# 1-Schematic_Hack_Club_2.net
KiCad netlist of a schematic drawn in EasyEDA
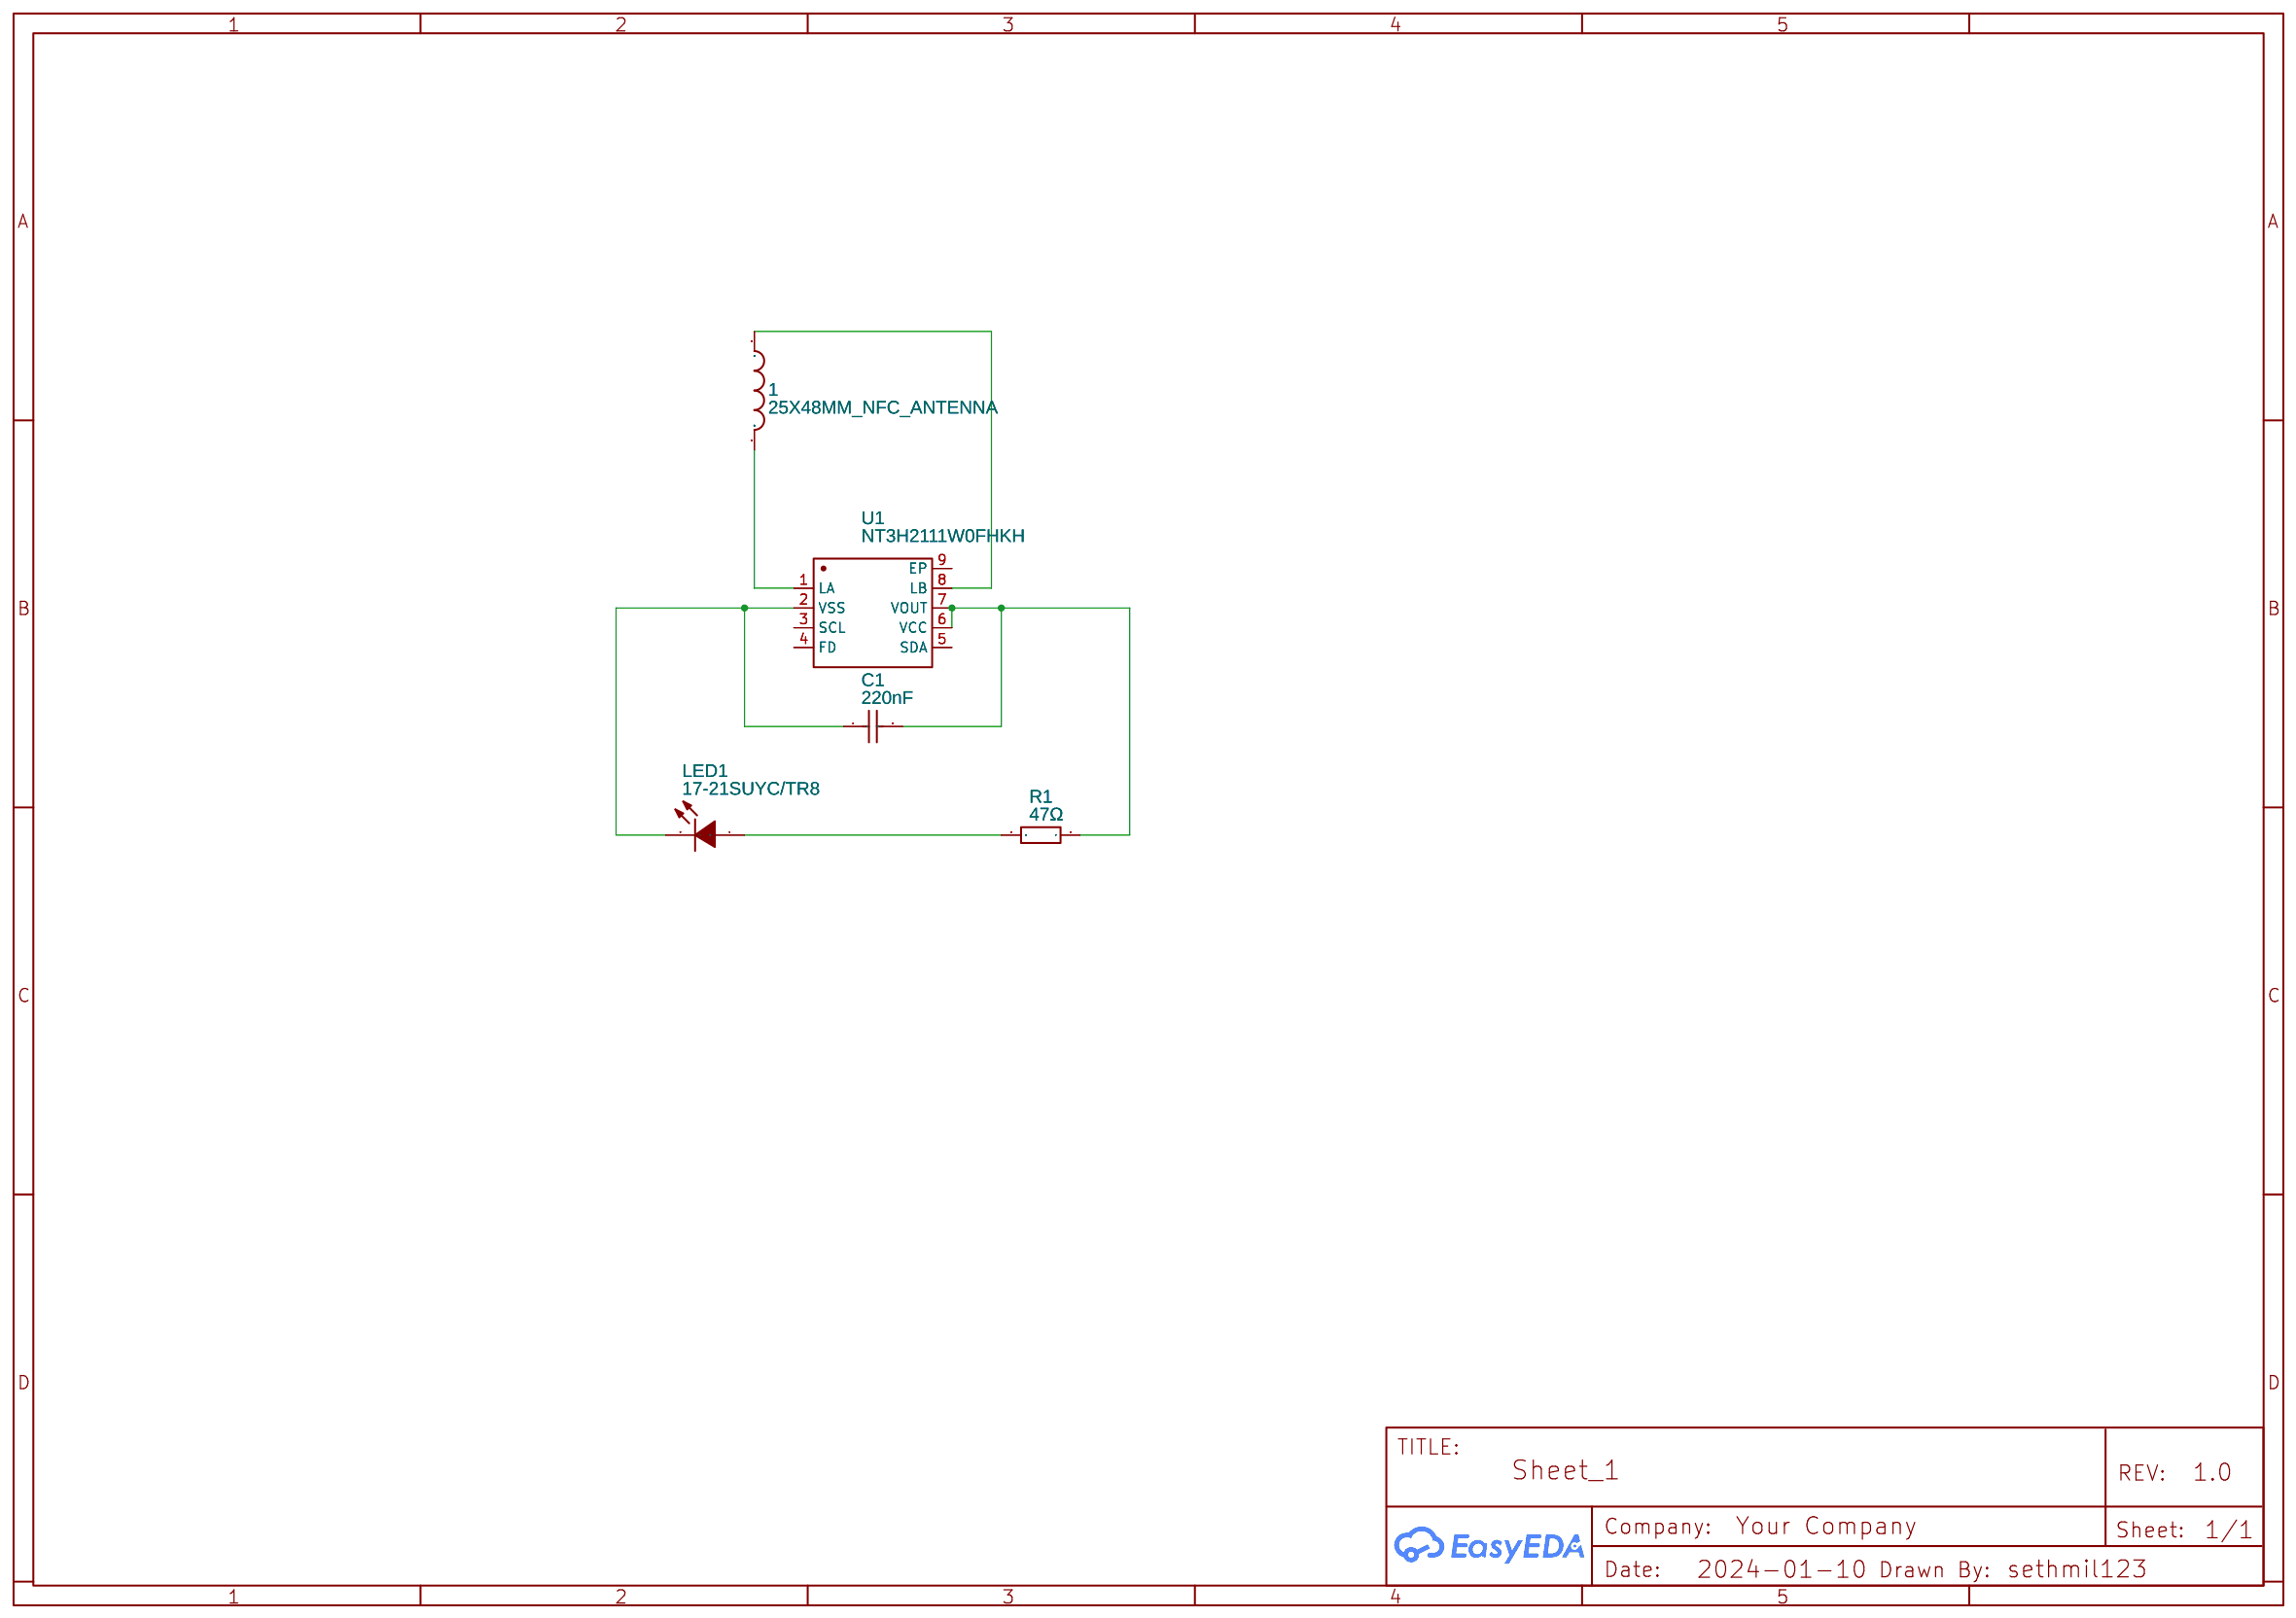
[diagram p0: schematic sheet]

(export (version "E")
  (design (tool "Eeschema 10.0.6"))
  (components
    (comp (ref "1") (value "25X48MM_NFC_ANTENNA") (libsource (lib "") (part "25X48MM_NFC_ANTENNA")))
    (comp (ref "C1")
      (value "220nF")
      (fields
        (field (name "Manufacturer Part") "CL10B224KA8NNNC")
        (field (name "Manufacturer") "SAMSUNG(三星)")
      )
      (libsource (lib "") (part "CL10B224KA8NNNC"))
    )
    (comp (ref "LED1")
      (value "17-21SUYC/TR8")
      (fields (field (name "Manufacturer Part") "KT-0805黄灯") (field (name "Manufacturer") "KENTO"))
      (libsource (lib "") (part "17-21SUYC/TR8"))
    )
    (comp (ref "R1")
      (value "47Ω")
      (fields
        (field (name "Manufacturer Part") "0603WAF470JT5E")
        (field (name "Manufacturer") "UNI-ROYAL(厚声)")
      )
      (libsource (lib "") (part "0603WAF470JT5E"))
    )
    (comp (ref "U1")
      (value "NT3H2111W0FHKH")
      (fields (field (name "Manufacturer") "NXP(恩智浦)"))
      (libsource (lib "") (part "NT3H2111W0FHKH"))
    )
  )
  (nets
    (net (code "1") (name "Net-(LED1-+)") (class "Default")
      (node (ref "LED1") (pin "1") (pinfunction "+_1") (pintype "unspecified"))
      (node (ref "R1") (pin "1") (pinfunction "1_1") (pintype "input"))
    )
    (net (code "2") (name "Net-(LED1--)") (class "Default")
      (node (ref "C1") (pin "1") (pinfunction "1_1") (pintype "input"))
      (node (ref "LED1") (pin "2") (pinfunction "-_2") (pintype "unspecified"))
      (node (ref "U1") (pin "2") (pinfunction "VSS_2") (pintype "unspecified"))
    )
    (net (code "3") (name "Net-(U1-LA)") (class "Default")
      (node (ref "1") (pin "P$2") (pinfunction "P$2_P$2") (pintype "bidirectional"))
      (node (ref "U1") (pin "1") (pinfunction "LA_1") (pintype "unspecified"))
    )
    (net (code "4") (name "Net-(U1-LB)") (class "Default")
      (node (ref "1") (pin "P$1") (pinfunction "P$1_P$1") (pintype "bidirectional"))
      (node (ref "U1") (pin "8") (pinfunction "LB_8") (pintype "unspecified"))
    )
    (net (code "5") (name "Net-(U1-VCC)") (class "Default")
      (node (ref "C1") (pin "2") (pinfunction "2_2") (pintype "input"))
      (node (ref "R1") (pin "2") (pinfunction "2_2") (pintype "input"))
      (node (ref "U1") (pin "6") (pinfunction "VCC_6") (pintype "unspecified"))
      (node (ref "U1") (pin "7") (pinfunction "VOUT_7") (pintype "unspecified"))
    )
    (net (code "6") (name "unconnected-(U1-EP-Pad9)") (class "Default")
      (node (ref "U1") (pin "9") (pinfunction "EP_9") (pintype "unspecified"))
    )
    (net (code "7") (name "unconnected-(U1-FD-Pad4)") (class "Default")
      (node (ref "U1") (pin "4") (pinfunction "FD_4") (pintype "unspecified"))
    )
    (net (code "8") (name "unconnected-(U1-SCL-Pad3)") (class "Default")
      (node (ref "U1") (pin "3") (pinfunction "SCL_3") (pintype "unspecified"))
    )
    (net (code "9") (name "unconnected-(U1-SDA-Pad5)") (class "Default")
      (node (ref "U1") (pin "5") (pinfunction "SDA_5") (pintype "unspecified"))
    )
  )
)
